# PotentialGainSensor.net
KiCad netlist of a schematic drawn in EAGLE
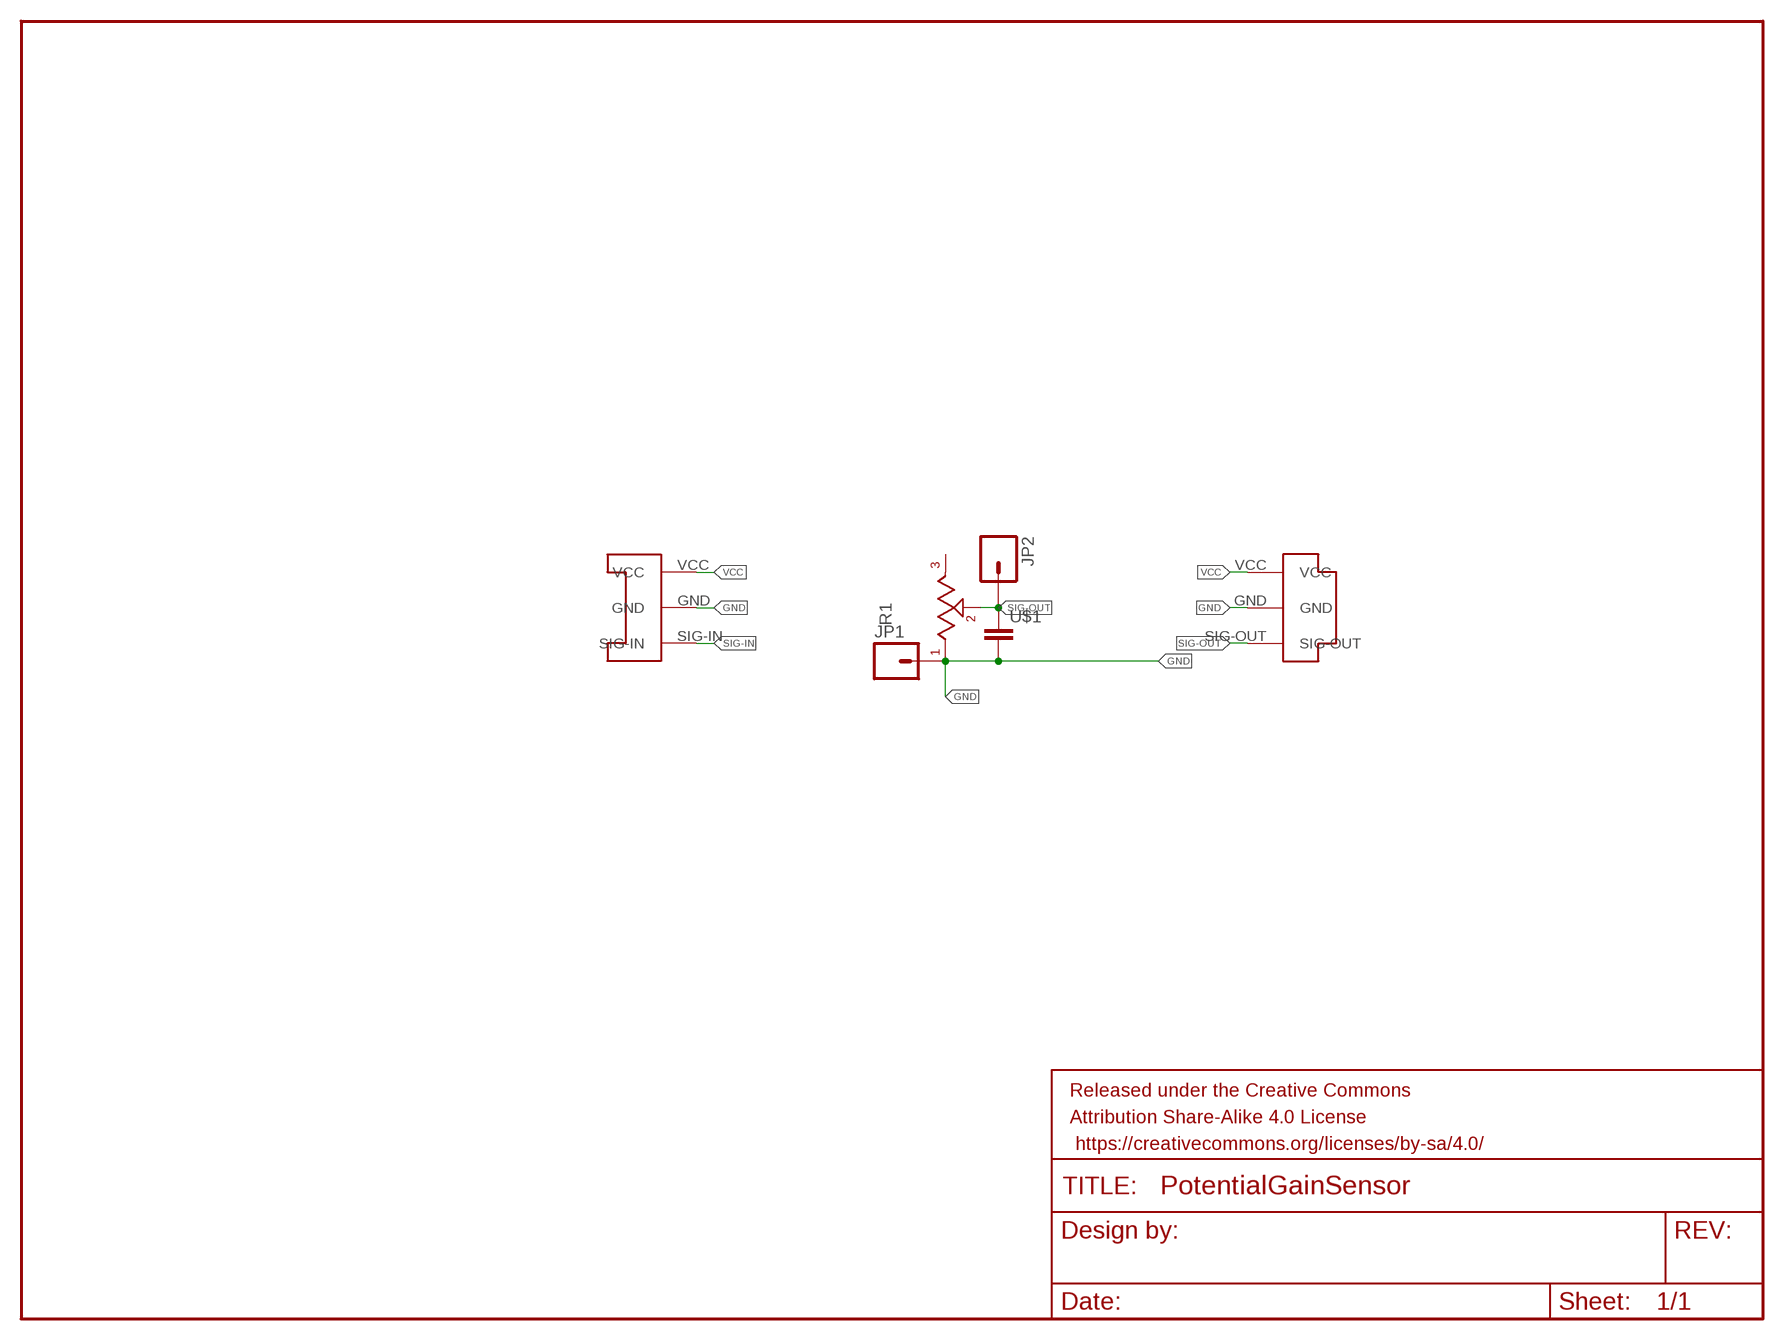
[diagram p0: schematic, sheet 1]

(export (version "E")
  (design (tool "Eeschema 10.0.6"))
  (components
    (comp (ref "FRAME1")
      (value "FRAME-LETTERNO_PACKAGE")
      (footprint "eagle-import:DUMMY")
      (fields (field (name "DESIGNER") "Nobody"))
      (libsource (lib "eagle-import") (part "FRAME-LETTERNO_PACKAGE"))
    )
    (comp (ref "JP1")
      (value "M01SPRING-CONN")
      (footprint "eagle-import:SPRING-CONNECTOR")
      (libsource (lib "eagle-import") (part "M01SPRING-CONN"))
    )
    (comp (ref "JP2")
      (value "M01SPRING-CONN")
      (footprint "eagle-import:SPRING-CONNECTOR")
      (libsource (lib "eagle-import") (part "M01SPRING-CONN"))
    )
    (comp (ref "R1")
      (value "POT-TRIM-SMD-BOURNS-3314J-1")
      (footprint "eagle-import:POT-TRIM-SMD-BOURNS-3314")
      (libsource (lib "eagle-import") (part "POT-TRIM-SMD-BOURNS-3314J-1"))
    )
    (comp (ref "U$1")
      (value "CAPCAP-0805")
      (footprint "eagle-import:CAP-0805")
      (libsource (lib "eagle-import") (part "CAPCAP-0805"))
    )
    (comp (ref "U$2")
      (value "CONN-PLUG-3POS-3MM")
      (footprint "eagle-import:PLUG-3POS-3MM-SMD")
      (libsource (lib "eagle-import") (part "CONN-PLUG-3POS-3MM"))
    )
    (comp (ref "U$3")
      (value "CONN-SOCKET-3POS-3MM")
      (footprint "eagle-import:SOCKET-3POS-3MM-SMD")
      (libsource (lib "eagle-import") (part "CONN-SOCKET-3POS-3MM"))
    )
  )
  (nets
    (net (code "1") (name "GND") (class "Default")
      (node (ref "JP1") (pin "P$2") (pinfunction "1_P$2") (pintype "passive"))
      (node (ref "R1") (pin "3") (pinfunction "1_3") (pintype "passive"))
      (node (ref "U$1") (pin "2") (pinfunction "2_2") (pintype "passive"))
      (node (ref "U$2") (pin "GND") (pinfunction "GND_GND") (pintype "power_in"))
      (node (ref "U$3") (pin "GND") (pinfunction "GND_GND") (pintype "power_in"))
    )
    (net (code "2") (name "SIG-IN") (class "Default")
      (node (ref "U$3") (pin "SIG-IN") (pinfunction "SIG-IN_SIG-IN") (pintype "bidirectional"))
    )
    (net (code "3") (name "SIG-OUT") (class "Default")
      (node (ref "JP2") (pin "P$2") (pinfunction "1_P$2") (pintype "passive"))
      (node (ref "R1") (pin "2") (pinfunction "2_2") (pintype "passive"))
      (node (ref "U$1") (pin "1") (pinfunction "1_1") (pintype "passive"))
      (node (ref "U$2") (pin "SIG-OUT") (pinfunction "SIG-OUT_SIG-OUT") (pintype "bidirectional"))
    )
    (net (code "4") (name "VCC") (class "Default")
      (node (ref "U$2") (pin "VCC") (pinfunction "VCC_VCC") (pintype "power_in"))
      (node (ref "U$3") (pin "VCC") (pinfunction "VCC_VCC") (pintype "power_in"))
    )
    (net (code "5") (name "unconnected-(R1-3-Pad1)") (class "Default")
      (node (ref "R1") (pin "1") (pinfunction "3_1") (pintype "passive"))
    )
  )
)
